# Midi_LED_Rings_Black_10x5_gerbers_v4.net
KiCad netlist of a schematic drawn in EAGLE
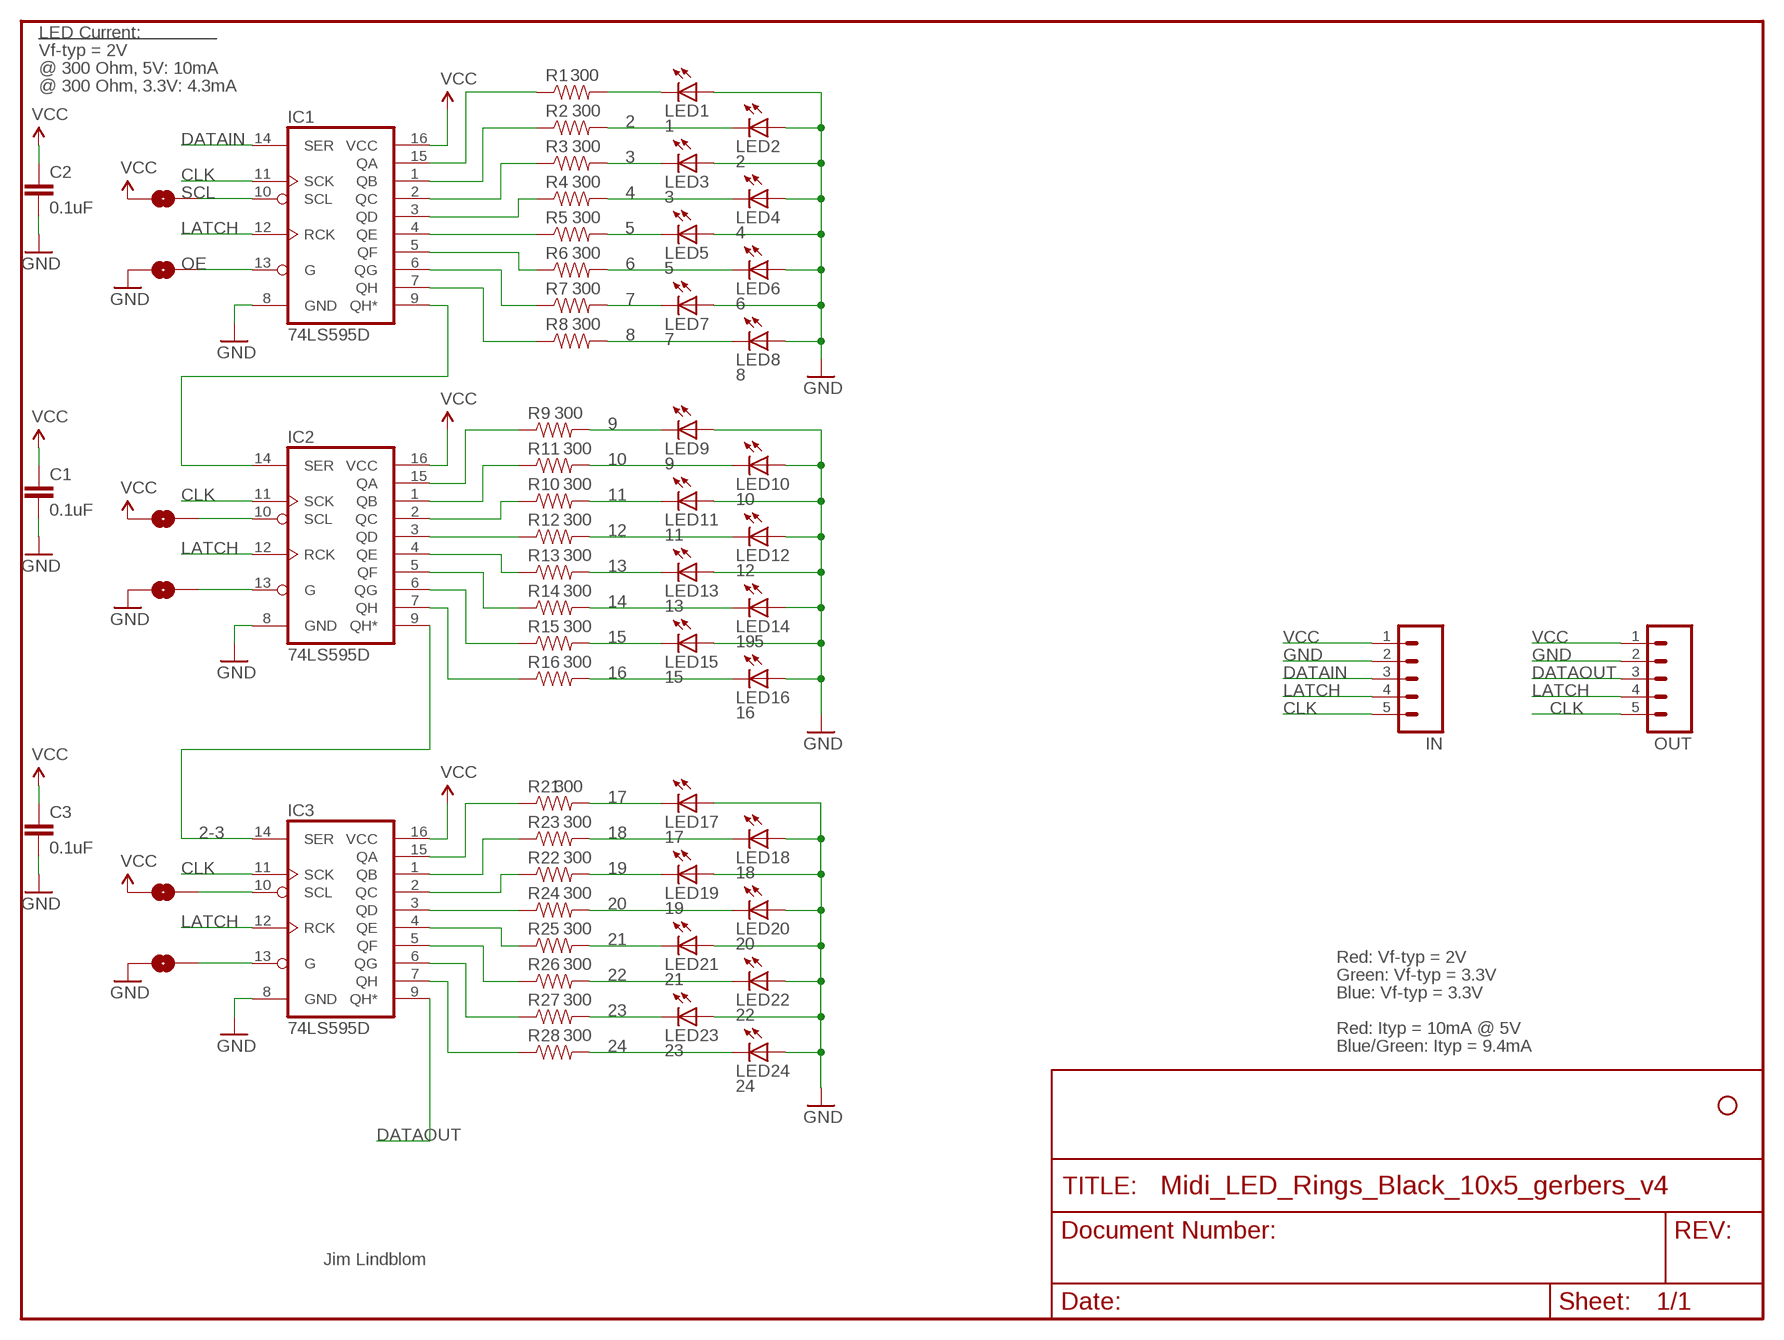
[diagram p0: schematic, sheet 1]

(export (version "E")
  (design (tool "Eeschema 10.0.6"))
  (components
    (comp (ref "C1")
      (value "0.1uF")
      (footprint "eagle-import:0402-CAP")
      (libsource (lib "eagle-import") (part "CAP0402-CAP"))
    )
    (comp (ref "C2")
      (value "0.1uF")
      (footprint "eagle-import:0402-CAP")
      (libsource (lib "eagle-import") (part "CAP0402-CAP"))
    )
    (comp (ref "C3")
      (value "0.1uF")
      (footprint "eagle-import:0402-CAP")
      (libsource (lib "eagle-import") (part "CAP0402-CAP"))
    )
    (comp (ref "IC1")
      (value "74LS595D")
      (footprint "eagle-import:SO16")
      (libsource (lib "eagle-import") (part "74595DLS"))
    )
    (comp (ref "IC2")
      (value "74LS595D")
      (footprint "eagle-import:SO16")
      (libsource (lib "eagle-import") (part "74595DLS"))
    )
    (comp (ref "IC3")
      (value "74LS595D")
      (footprint "eagle-import:SO16")
      (libsource (lib "eagle-import") (part "74595DLS"))
    )
    (comp (ref "IN")
      (value "M05LOCK")
      (footprint "eagle-import:1X05_LOCK")
      (libsource (lib "eagle-import") (part "M05LOCK"))
    )
    (comp (ref "JP12")
      (value "STAND-OFF")
      (footprint "eagle-import:STAND-OFF")
      (libsource (lib "eagle-import") (part "STAND-OFF"))
    )
    (comp (ref "LED1")
      (value "1")
      (footprint "eagle-import:LED-1206")
      (libsource (lib "eagle-import") (part "LED1206"))
    )
    (comp (ref "LED2")
      (value "2")
      (footprint "eagle-import:LED-1206")
      (libsource (lib "eagle-import") (part "LED1206"))
    )
    (comp (ref "LED3")
      (value "3")
      (footprint "eagle-import:LED-1206")
      (libsource (lib "eagle-import") (part "LED1206"))
    )
    (comp (ref "LED4")
      (value "4")
      (footprint "eagle-import:LED-1206")
      (libsource (lib "eagle-import") (part "LED1206"))
    )
    (comp (ref "LED5")
      (value "5")
      (footprint "eagle-import:LED-1206")
      (libsource (lib "eagle-import") (part "LED1206"))
    )
    (comp (ref "LED6")
      (value "6")
      (footprint "eagle-import:LED-1206")
      (libsource (lib "eagle-import") (part "LED1206"))
    )
    (comp (ref "LED7")
      (value "7")
      (footprint "eagle-import:LED-1206")
      (libsource (lib "eagle-import") (part "LED1206"))
    )
    (comp (ref "LED8")
      (value "8")
      (footprint "eagle-import:LED-1206")
      (libsource (lib "eagle-import") (part "LED1206"))
    )
    (comp (ref "LED9")
      (value "9")
      (footprint "eagle-import:LED-1206")
      (libsource (lib "eagle-import") (part "LED1206"))
    )
    (comp (ref "LED10")
      (value "10")
      (footprint "eagle-import:LED-1206")
      (libsource (lib "eagle-import") (part "LED1206"))
    )
    (comp (ref "LED11")
      (value "11")
      (footprint "eagle-import:LED-1206")
      (libsource (lib "eagle-import") (part "LED1206"))
    )
    (comp (ref "LED12")
      (value "12")
      (footprint "eagle-import:LED-1206")
      (libsource (lib "eagle-import") (part "LED1206"))
    )
    (comp (ref "LED13")
      (value "13")
      (footprint "eagle-import:LED-1206")
      (libsource (lib "eagle-import") (part "LED1206"))
    )
    (comp (ref "LED14")
      (value "195")
      (footprint "eagle-import:LED-1206")
      (libsource (lib "eagle-import") (part "LED1206"))
    )
    (comp (ref "LED15")
      (value "15")
      (footprint "eagle-import:LED-1206")
      (libsource (lib "eagle-import") (part "LED1206"))
    )
    (comp (ref "LED16")
      (value "16")
      (footprint "eagle-import:LED-1206")
      (libsource (lib "eagle-import") (part "LED1206"))
    )
    (comp (ref "LED17")
      (value "17")
      (footprint "eagle-import:LED-1206")
      (libsource (lib "eagle-import") (part "LED1206"))
    )
    (comp (ref "LED18")
      (value "18")
      (footprint "eagle-import:LED-1206")
      (libsource (lib "eagle-import") (part "LED1206"))
    )
    (comp (ref "LED19")
      (value "19")
      (footprint "eagle-import:LED-1206")
      (libsource (lib "eagle-import") (part "LED1206"))
    )
    (comp (ref "LED20")
      (value "20")
      (footprint "eagle-import:LED-1206")
      (libsource (lib "eagle-import") (part "LED1206"))
    )
    (comp (ref "LED21")
      (value "21")
      (footprint "eagle-import:LED-1206")
      (libsource (lib "eagle-import") (part "LED1206"))
    )
    (comp (ref "LED22")
      (value "22")
      (footprint "eagle-import:LED-1206")
      (libsource (lib "eagle-import") (part "LED1206"))
    )
    (comp (ref "LED23")
      (value "23")
      (footprint "eagle-import:LED-1206")
      (libsource (lib "eagle-import") (part "LED1206"))
    )
    (comp (ref "LED24")
      (value "24")
      (footprint "eagle-import:LED-1206")
      (libsource (lib "eagle-import") (part "LED1206"))
    )
    (comp (ref "OUT")
      (value "M05LOCK")
      (footprint "eagle-import:1X05_LOCK")
      (libsource (lib "eagle-import") (part "M05LOCK"))
    )
    (comp (ref "R1")
      (value "300")
      (footprint "eagle-import:0805")
      (libsource (lib "eagle-import") (part "RESISTOR0805-RES"))
    )
    (comp (ref "R2")
      (value "300")
      (footprint "eagle-import:0805")
      (libsource (lib "eagle-import") (part "RESISTOR0805-RES"))
    )
    (comp (ref "R3")
      (value "300")
      (footprint "eagle-import:0805")
      (libsource (lib "eagle-import") (part "RESISTOR0805-RES"))
    )
    (comp (ref "R4")
      (value "300")
      (footprint "eagle-import:0805")
      (libsource (lib "eagle-import") (part "RESISTOR0805-RES"))
    )
    (comp (ref "R5")
      (value "300")
      (footprint "eagle-import:0805")
      (libsource (lib "eagle-import") (part "RESISTOR0805-RES"))
    )
    (comp (ref "R6")
      (value "300")
      (footprint "eagle-import:0805")
      (libsource (lib "eagle-import") (part "RESISTOR0805-RES"))
    )
    (comp (ref "R7")
      (value "300")
      (footprint "eagle-import:0805")
      (libsource (lib "eagle-import") (part "RESISTOR0805-RES"))
    )
    (comp (ref "R8")
      (value "300")
      (footprint "eagle-import:0805")
      (libsource (lib "eagle-import") (part "RESISTOR0805-RES"))
    )
    (comp (ref "R9")
      (value "300")
      (footprint "eagle-import:0805")
      (libsource (lib "eagle-import") (part "RESISTOR0805-RES"))
    )
    (comp (ref "R10")
      (value "300")
      (footprint "eagle-import:0805")
      (libsource (lib "eagle-import") (part "RESISTOR0805-RES"))
    )
    (comp (ref "R11")
      (value "300")
      (footprint "eagle-import:0805")
      (libsource (lib "eagle-import") (part "RESISTOR0805-RES"))
    )
    (comp (ref "R12")
      (value "300")
      (footprint "eagle-import:0805")
      (libsource (lib "eagle-import") (part "RESISTOR0805-RES"))
    )
    (comp (ref "R13")
      (value "300")
      (footprint "eagle-import:0805")
      (libsource (lib "eagle-import") (part "RESISTOR0805-RES"))
    )
    (comp (ref "R14")
      (value "300")
      (footprint "eagle-import:0805")
      (libsource (lib "eagle-import") (part "RESISTOR0805-RES"))
    )
    (comp (ref "R15")
      (value "300")
      (footprint "eagle-import:0805")
      (libsource (lib "eagle-import") (part "RESISTOR0805-RES"))
    )
    (comp (ref "R16")
      (value "300")
      (footprint "eagle-import:0805")
      (libsource (lib "eagle-import") (part "RESISTOR0805-RES"))
    )
    (comp (ref "R21")
      (value "300")
      (footprint "eagle-import:0805")
      (libsource (lib "eagle-import") (part "RESISTOR0805-RES"))
    )
    (comp (ref "R22")
      (value "300")
      (footprint "eagle-import:0805")
      (libsource (lib "eagle-import") (part "RESISTOR0805-RES"))
    )
    (comp (ref "R23")
      (value "300")
      (footprint "eagle-import:0805")
      (libsource (lib "eagle-import") (part "RESISTOR0805-RES"))
    )
    (comp (ref "R24")
      (value "300")
      (footprint "eagle-import:0805")
      (libsource (lib "eagle-import") (part "RESISTOR0805-RES"))
    )
    (comp (ref "R25")
      (value "300")
      (footprint "eagle-import:0805")
      (libsource (lib "eagle-import") (part "RESISTOR0805-RES"))
    )
    (comp (ref "R26")
      (value "300")
      (footprint "eagle-import:0805")
      (libsource (lib "eagle-import") (part "RESISTOR0805-RES"))
    )
    (comp (ref "R27")
      (value "300")
      (footprint "eagle-import:0805")
      (libsource (lib "eagle-import") (part "RESISTOR0805-RES"))
    )
    (comp (ref "R28")
      (value "300")
      (footprint "eagle-import:0805")
      (libsource (lib "eagle-import") (part "RESISTOR0805-RES"))
    )
    (comp (ref "SJ1")
      (value "SOLDERJUMPERTRACE")
      (footprint "eagle-import:SJ_2S-TRACE")
      (libsource (lib "eagle-import") (part "SOLDERJUMPERTRACE"))
    )
    (comp (ref "SJ2")
      (value "SOLDERJUMPERTRACE")
      (footprint "eagle-import:SJ_2S-TRACE")
      (libsource (lib "eagle-import") (part "SOLDERJUMPERTRACE"))
    )
    (comp (ref "SJ3")
      (value "SOLDERJUMPERTRACE")
      (footprint "eagle-import:SJ_2S-TRACE")
      (libsource (lib "eagle-import") (part "SOLDERJUMPERTRACE"))
    )
    (comp (ref "SJ4")
      (value "SOLDERJUMPERTRACE")
      (footprint "eagle-import:SJ_2S-TRACE")
      (libsource (lib "eagle-import") (part "SOLDERJUMPERTRACE"))
    )
    (comp (ref "SJ5")
      (value "SOLDERJUMPERTRACE")
      (footprint "eagle-import:SJ_2S-TRACE")
      (libsource (lib "eagle-import") (part "SOLDERJUMPERTRACE"))
    )
    (comp (ref "SJ6")
      (value "SOLDERJUMPERTRACE")
      (footprint "eagle-import:SJ_2S-TRACE")
      (libsource (lib "eagle-import") (part "SOLDERJUMPERTRACE"))
    )
  )
  (nets
    (net (code "1") (name "/2") (class "Default")
      (node (ref "LED2") (pin "C") (pinfunction "C_C") (pintype "passive"))
      (node (ref "R2") (pin "2") (pinfunction "2_2") (pintype "passive"))
    )
    (net (code "2") (name "/2-3") (class "Default")
      (node (ref "IC2") (pin "9") (pinfunction "QH*_9") (pintype "tri_state"))
      (node (ref "IC3") (pin "14") (pinfunction "SER_14") (pintype "input"))
    )
    (net (code "3") (name "/3") (class "Default")
      (node (ref "LED3") (pin "C") (pinfunction "C_C") (pintype "passive"))
      (node (ref "R3") (pin "2") (pinfunction "2_2") (pintype "passive"))
    )
    (net (code "4") (name "/4") (class "Default")
      (node (ref "LED4") (pin "C") (pinfunction "C_C") (pintype "passive"))
      (node (ref "R4") (pin "2") (pinfunction "2_2") (pintype "passive"))
    )
    (net (code "5") (name "/5") (class "Default")
      (node (ref "LED5") (pin "C") (pinfunction "C_C") (pintype "passive"))
      (node (ref "R5") (pin "2") (pinfunction "2_2") (pintype "passive"))
    )
    (net (code "6") (name "/6") (class "Default")
      (node (ref "LED6") (pin "C") (pinfunction "C_C") (pintype "passive"))
      (node (ref "R6") (pin "2") (pinfunction "2_2") (pintype "passive"))
    )
    (net (code "7") (name "/7") (class "Default")
      (node (ref "LED7") (pin "C") (pinfunction "C_C") (pintype "passive"))
      (node (ref "R7") (pin "2") (pinfunction "2_2") (pintype "passive"))
    )
    (net (code "8") (name "/8") (class "Default")
      (node (ref "LED8") (pin "C") (pinfunction "C_C") (pintype "passive"))
      (node (ref "R8") (pin "2") (pinfunction "2_2") (pintype "passive"))
    )
    (net (code "9") (name "/9") (class "Default")
      (node (ref "LED9") (pin "C") (pinfunction "C_C") (pintype "passive"))
      (node (ref "R9") (pin "2") (pinfunction "2_2") (pintype "passive"))
    )
    (net (code "10") (name "/10") (class "Default")
      (node (ref "LED10") (pin "C") (pinfunction "C_C") (pintype "passive"))
      (node (ref "R11") (pin "2") (pinfunction "2_2") (pintype "passive"))
    )
    (net (code "11") (name "/11") (class "Default")
      (node (ref "LED11") (pin "C") (pinfunction "C_C") (pintype "passive"))
      (node (ref "R10") (pin "2") (pinfunction "2_2") (pintype "passive"))
    )
    (net (code "12") (name "/12") (class "Default")
      (node (ref "LED12") (pin "C") (pinfunction "C_C") (pintype "passive"))
      (node (ref "R12") (pin "2") (pinfunction "2_2") (pintype "passive"))
    )
    (net (code "13") (name "/13") (class "Default")
      (node (ref "LED13") (pin "C") (pinfunction "C_C") (pintype "passive"))
      (node (ref "R13") (pin "2") (pinfunction "2_2") (pintype "passive"))
    )
    (net (code "14") (name "/14") (class "Default")
      (node (ref "LED14") (pin "C") (pinfunction "C_C") (pintype "passive"))
      (node (ref "R14") (pin "2") (pinfunction "2_2") (pintype "passive"))
    )
    (net (code "15") (name "/15") (class "Default")
      (node (ref "LED15") (pin "C") (pinfunction "C_C") (pintype "passive"))
      (node (ref "R15") (pin "2") (pinfunction "2_2") (pintype "passive"))
    )
    (net (code "16") (name "/16") (class "Default")
      (node (ref "LED16") (pin "C") (pinfunction "C_C") (pintype "passive"))
      (node (ref "R16") (pin "2") (pinfunction "2_2") (pintype "passive"))
    )
    (net (code "17") (name "/17") (class "Default")
      (node (ref "LED17") (pin "C") (pinfunction "C_C") (pintype "passive"))
      (node (ref "R21") (pin "2") (pinfunction "2_2") (pintype "passive"))
    )
    (net (code "18") (name "/18") (class "Default")
      (node (ref "LED18") (pin "C") (pinfunction "C_C") (pintype "passive"))
      (node (ref "R23") (pin "2") (pinfunction "2_2") (pintype "passive"))
    )
    (net (code "19") (name "/19") (class "Default")
      (node (ref "LED19") (pin "C") (pinfunction "C_C") (pintype "passive"))
      (node (ref "R22") (pin "2") (pinfunction "2_2") (pintype "passive"))
    )
    (net (code "20") (name "/20") (class "Default")
      (node (ref "LED20") (pin "C") (pinfunction "C_C") (pintype "passive"))
      (node (ref "R24") (pin "2") (pinfunction "2_2") (pintype "passive"))
    )
    (net (code "21") (name "/21") (class "Default")
      (node (ref "LED21") (pin "C") (pinfunction "C_C") (pintype "passive"))
      (node (ref "R25") (pin "2") (pinfunction "2_2") (pintype "passive"))
    )
    (net (code "22") (name "/22") (class "Default")
      (node (ref "LED22") (pin "C") (pinfunction "C_C") (pintype "passive"))
      (node (ref "R26") (pin "2") (pinfunction "2_2") (pintype "passive"))
    )
    (net (code "23") (name "/23") (class "Default")
      (node (ref "LED23") (pin "C") (pinfunction "C_C") (pintype "passive"))
      (node (ref "R27") (pin "2") (pinfunction "2_2") (pintype "passive"))
    )
    (net (code "24") (name "/24") (class "Default")
      (node (ref "LED24") (pin "C") (pinfunction "C_C") (pintype "passive"))
      (node (ref "R28") (pin "2") (pinfunction "2_2") (pintype "passive"))
    )
    (net (code "25") (name "/CLK") (class "Default")
      (node (ref "IC1") (pin "11") (pinfunction "SCK_11") (pintype "input"))
      (node (ref "IC2") (pin "11") (pinfunction "SCK_11") (pintype "input"))
      (node (ref "IC3") (pin "11") (pinfunction "SCK_11") (pintype "input"))
      (node (ref "IN") (pin "5") (pinfunction "5_5") (pintype "passive"))
      (node (ref "OUT") (pin "5") (pinfunction "5_5") (pintype "passive"))
    )
    (net (code "26") (name "/DATAIN") (class "Default")
      (node (ref "IC1") (pin "14") (pinfunction "SER_14") (pintype "input"))
      (node (ref "IN") (pin "3") (pinfunction "3_3") (pintype "passive"))
    )
    (net (code "27") (name "/DATAOUT") (class "Default")
      (node (ref "IC3") (pin "9") (pinfunction "QH*_9") (pintype "tri_state"))
      (node (ref "OUT") (pin "3") (pinfunction "3_3") (pintype "passive"))
    )
    (net (code "28") (name "/LATCH") (class "Default")
      (node (ref "IC1") (pin "12") (pinfunction "RCK_12") (pintype "input"))
      (node (ref "IC2") (pin "12") (pinfunction "RCK_12") (pintype "input"))
      (node (ref "IC3") (pin "12") (pinfunction "RCK_12") (pintype "input"))
      (node (ref "IN") (pin "4") (pinfunction "4_4") (pintype "passive"))
      (node (ref "OUT") (pin "4") (pinfunction "4_4") (pintype "passive"))
    )
    (net (code "29") (name "/OE") (class "Default")
      (node (ref "IC1") (pin "13") (pinfunction "G_13") (pintype "input"))
      (node (ref "SJ2") (pin "2") (pinfunction "2_2") (pintype "passive"))
    )
    (net (code "30") (name "/SCL") (class "Default")
      (node (ref "IC1") (pin "10") (pinfunction "SCL_10") (pintype "input"))
      (node (ref "SJ1") (pin "2") (pinfunction "2_2") (pintype "passive"))
    )
    (net (code "31") (name "GND") (class "Default")
      (node (ref "C1") (pin "2") (pinfunction "2_2") (pintype "passive"))
      (node (ref "C2") (pin "2") (pinfunction "2_2") (pintype "passive"))
      (node (ref "C3") (pin "2") (pinfunction "2_2") (pintype "passive"))
      (node (ref "IC1") (pin "8") (pinfunction "GND_8") (pintype "power_in"))
      (node (ref "IC2") (pin "8") (pinfunction "GND_8") (pintype "power_in"))
      (node (ref "IC3") (pin "8") (pinfunction "GND_8") (pintype "power_in"))
      (node (ref "IN") (pin "2") (pinfunction "2_2") (pintype "passive"))
      (node (ref "LED1") (pin "A") (pinfunction "A_A") (pintype "passive"))
      (node (ref "LED10") (pin "A") (pinfunction "A_A") (pintype "passive"))
      (node (ref "LED11") (pin "A") (pinfunction "A_A") (pintype "passive"))
      (node (ref "LED12") (pin "A") (pinfunction "A_A") (pintype "passive"))
      (node (ref "LED13") (pin "A") (pinfunction "A_A") (pintype "passive"))
      (node (ref "LED14") (pin "A") (pinfunction "A_A") (pintype "passive"))
      (node (ref "LED15") (pin "A") (pinfunction "A_A") (pintype "passive"))
      (node (ref "LED16") (pin "A") (pinfunction "A_A") (pintype "passive"))
      (node (ref "LED17") (pin "A") (pinfunction "A_A") (pintype "passive"))
      (node (ref "LED18") (pin "A") (pinfunction "A_A") (pintype "passive"))
      (node (ref "LED19") (pin "A") (pinfunction "A_A") (pintype "passive"))
      (node (ref "LED2") (pin "A") (pinfunction "A_A") (pintype "passive"))
      (node (ref "LED20") (pin "A") (pinfunction "A_A") (pintype "passive"))
      (node (ref "LED21") (pin "A") (pinfunction "A_A") (pintype "passive"))
      (node (ref "LED22") (pin "A") (pinfunction "A_A") (pintype "passive"))
      (node (ref "LED23") (pin "A") (pinfunction "A_A") (pintype "passive"))
      (node (ref "LED24") (pin "A") (pinfunction "A_A") (pintype "passive"))
      (node (ref "LED3") (pin "A") (pinfunction "A_A") (pintype "passive"))
      (node (ref "LED4") (pin "A") (pinfunction "A_A") (pintype "passive"))
      (node (ref "LED5") (pin "A") (pinfunction "A_A") (pintype "passive"))
      (node (ref "LED6") (pin "A") (pinfunction "A_A") (pintype "passive"))
      (node (ref "LED7") (pin "A") (pinfunction "A_A") (pintype "passive"))
      (node (ref "LED8") (pin "A") (pinfunction "A_A") (pintype "passive"))
      (node (ref "LED9") (pin "A") (pinfunction "A_A") (pintype "passive"))
      (node (ref "OUT") (pin "2") (pinfunction "2_2") (pintype "passive"))
      (node (ref "SJ2") (pin "1") (pinfunction "1_1") (pintype "passive"))
      (node (ref "SJ4") (pin "1") (pinfunction "1_1") (pintype "passive"))
      (node (ref "SJ6") (pin "1") (pinfunction "1_1") (pintype "passive"))
    )
    (net (code "32") (name "Net-(IC1-QA)") (class "Default")
      (node (ref "IC1") (pin "15") (pinfunction "QA_15") (pintype "tri_state"))
      (node (ref "R1") (pin "1") (pinfunction "1_1") (pintype "passive"))
    )
    (net (code "33") (name "Net-(IC1-QB)") (class "Default")
      (node (ref "IC1") (pin "1") (pinfunction "QB_1") (pintype "tri_state"))
      (node (ref "R2") (pin "1") (pinfunction "1_1") (pintype "passive"))
    )
    (net (code "34") (name "Net-(IC1-QC)") (class "Default")
      (node (ref "IC1") (pin "2") (pinfunction "QC_2") (pintype "tri_state"))
      (node (ref "R3") (pin "1") (pinfunction "1_1") (pintype "passive"))
    )
    (net (code "35") (name "Net-(IC1-QD)") (class "Default")
      (node (ref "IC1") (pin "3") (pinfunction "QD_3") (pintype "tri_state"))
      (node (ref "R4") (pin "1") (pinfunction "1_1") (pintype "passive"))
    )
    (net (code "36") (name "Net-(IC1-QE)") (class "Default")
      (node (ref "IC1") (pin "4") (pinfunction "QE_4") (pintype "tri_state"))
      (node (ref "R5") (pin "1") (pinfunction "1_1") (pintype "passive"))
    )
    (net (code "37") (name "Net-(IC1-QF)") (class "Default")
      (node (ref "IC1") (pin "5") (pinfunction "QF_5") (pintype "tri_state"))
      (node (ref "R6") (pin "1") (pinfunction "1_1") (pintype "passive"))
    )
    (net (code "38") (name "Net-(IC1-QG)") (class "Default")
      (node (ref "IC1") (pin "6") (pinfunction "QG_6") (pintype "tri_state"))
      (node (ref "R7") (pin "1") (pinfunction "1_1") (pintype "passive"))
    )
    (net (code "39") (name "Net-(IC1-QH)") (class "Default")
      (node (ref "IC1") (pin "7") (pinfunction "QH_7") (pintype "tri_state"))
      (node (ref "R8") (pin "1") (pinfunction "1_1") (pintype "passive"))
    )
    (net (code "40") (name "Net-(IC1-QH*)") (class "Default")
      (node (ref "IC1") (pin "9") (pinfunction "QH*_9") (pintype "tri_state"))
      (node (ref "IC2") (pin "14") (pinfunction "SER_14") (pintype "input"))
    )
    (net (code "41") (name "Net-(IC2-G)") (class "Default")
      (node (ref "IC2") (pin "13") (pinfunction "G_13") (pintype "input"))
      (node (ref "SJ4") (pin "2") (pinfunction "2_2") (pintype "passive"))
    )
    (net (code "42") (name "Net-(IC2-QA)") (class "Default")
      (node (ref "IC2") (pin "15") (pinfunction "QA_15") (pintype "tri_state"))
      (node (ref "R9") (pin "1") (pinfunction "1_1") (pintype "passive"))
    )
    (net (code "43") (name "Net-(IC2-QB)") (class "Default")
      (node (ref "IC2") (pin "1") (pinfunction "QB_1") (pintype "tri_state"))
      (node (ref "R11") (pin "1") (pinfunction "1_1") (pintype "passive"))
    )
    (net (code "44") (name "Net-(IC2-QC)") (class "Default")
      (node (ref "IC2") (pin "2") (pinfunction "QC_2") (pintype "tri_state"))
      (node (ref "R10") (pin "1") (pinfunction "1_1") (pintype "passive"))
    )
    (net (code "45") (name "Net-(IC2-QD)") (class "Default")
      (node (ref "IC2") (pin "3") (pinfunction "QD_3") (pintype "tri_state"))
      (node (ref "R12") (pin "1") (pinfunction "1_1") (pintype "passive"))
    )
    (net (code "46") (name "Net-(IC2-QE)") (class "Default")
      (node (ref "IC2") (pin "4") (pinfunction "QE_4") (pintype "tri_state"))
      (node (ref "R13") (pin "1") (pinfunction "1_1") (pintype "passive"))
    )
    (net (code "47") (name "Net-(IC2-QF)") (class "Default")
      (node (ref "IC2") (pin "5") (pinfunction "QF_5") (pintype "tri_state"))
      (node (ref "R14") (pin "1") (pinfunction "1_1") (pintype "passive"))
    )
    (net (code "48") (name "Net-(IC2-QG)") (class "Default")
      (node (ref "IC2") (pin "6") (pinfunction "QG_6") (pintype "tri_state"))
      (node (ref "R15") (pin "1") (pinfunction "1_1") (pintype "passive"))
    )
    (net (code "49") (name "Net-(IC2-QH)") (class "Default")
      (node (ref "IC2") (pin "7") (pinfunction "QH_7") (pintype "tri_state"))
      (node (ref "R16") (pin "1") (pinfunction "1_1") (pintype "passive"))
    )
    (net (code "50") (name "Net-(IC2-SCL)") (class "Default")
      (node (ref "IC2") (pin "10") (pinfunction "SCL_10") (pintype "input"))
      (node (ref "SJ3") (pin "2") (pinfunction "2_2") (pintype "passive"))
    )
    (net (code "51") (name "Net-(IC3-G)") (class "Default")
      (node (ref "IC3") (pin "13") (pinfunction "G_13") (pintype "input"))
      (node (ref "SJ6") (pin "2") (pinfunction "2_2") (pintype "passive"))
    )
    (net (code "52") (name "Net-(IC3-QA)") (class "Default")
      (node (ref "IC3") (pin "15") (pinfunction "QA_15") (pintype "tri_state"))
      (node (ref "R21") (pin "1") (pinfunction "1_1") (pintype "passive"))
    )
    (net (code "53") (name "Net-(IC3-QB)") (class "Default")
      (node (ref "IC3") (pin "1") (pinfunction "QB_1") (pintype "tri_state"))
      (node (ref "R23") (pin "1") (pinfunction "1_1") (pintype "passive"))
    )
    (net (code "54") (name "Net-(IC3-QC)") (class "Default")
      (node (ref "IC3") (pin "2") (pinfunction "QC_2") (pintype "tri_state"))
      (node (ref "R22") (pin "1") (pinfunction "1_1") (pintype "passive"))
    )
    (net (code "55") (name "Net-(IC3-QD)") (class "Default")
      (node (ref "IC3") (pin "3") (pinfunction "QD_3") (pintype "tri_state"))
      (node (ref "R24") (pin "1") (pinfunction "1_1") (pintype "passive"))
    )
    (net (code "56") (name "Net-(IC3-QE)") (class "Default")
      (node (ref "IC3") (pin "4") (pinfunction "QE_4") (pintype "tri_state"))
      (node (ref "R25") (pin "1") (pinfunction "1_1") (pintype "passive"))
    )
    (net (code "57") (name "Net-(IC3-QF)") (class "Default")
      (node (ref "IC3") (pin "5") (pinfunction "QF_5") (pintype "tri_state"))
      (node (ref "R26") (pin "1") (pinfunction "1_1") (pintype "passive"))
    )
    (net (code "58") (name "Net-(IC3-QG)") (class "Default")
      (node (ref "IC3") (pin "6") (pinfunction "QG_6") (pintype "tri_state"))
      (node (ref "R27") (pin "1") (pinfunction "1_1") (pintype "passive"))
    )
    (net (code "59") (name "Net-(IC3-QH)") (class "Default")
      (node (ref "IC3") (pin "7") (pinfunction "QH_7") (pintype "tri_state"))
      (node (ref "R28") (pin "1") (pinfunction "1_1") (pintype "passive"))
    )
    (net (code "60") (name "Net-(IC3-SCL)") (class "Default")
      (node (ref "IC3") (pin "10") (pinfunction "SCL_10") (pintype "input"))
      (node (ref "SJ5") (pin "2") (pinfunction "2_2") (pintype "passive"))
    )
    (net (code "61") (name "Net-(LED1-PadC)") (class "Default")
      (node (ref "LED1") (pin "C") (pinfunction "C_C") (pintype "passive"))
      (node (ref "R1") (pin "2") (pinfunction "2_2") (pintype "passive"))
    )
    (net (code "62") (name "VCC") (class "Default")
      (node (ref "C1") (pin "1") (pinfunction "1_1") (pintype "passive"))
      (node (ref "C2") (pin "1") (pinfunction "1_1") (pintype "passive"))
      (node (ref "C3") (pin "1") (pinfunction "1_1") (pintype "passive"))
      (node (ref "IC1") (pin "16") (pinfunction "VCC_16") (pintype "power_in"))
      (node (ref "IC2") (pin "16") (pinfunction "VCC_16") (pintype "power_in"))
      (node (ref "IC3") (pin "16") (pinfunction "VCC_16") (pintype "power_in"))
      (node (ref "IN") (pin "1") (pinfunction "1_1") (pintype "passive"))
      (node (ref "OUT") (pin "1") (pinfunction "1_1") (pintype "passive"))
      (node (ref "SJ1") (pin "1") (pinfunction "1_1") (pintype "passive"))
      (node (ref "SJ3") (pin "1") (pinfunction "1_1") (pintype "passive"))
      (node (ref "SJ5") (pin "1") (pinfunction "1_1") (pintype "passive"))
    )
  )
)
